# Esquematico_V2.net
KiCad netlist of a schematic drawn in Altium Designer
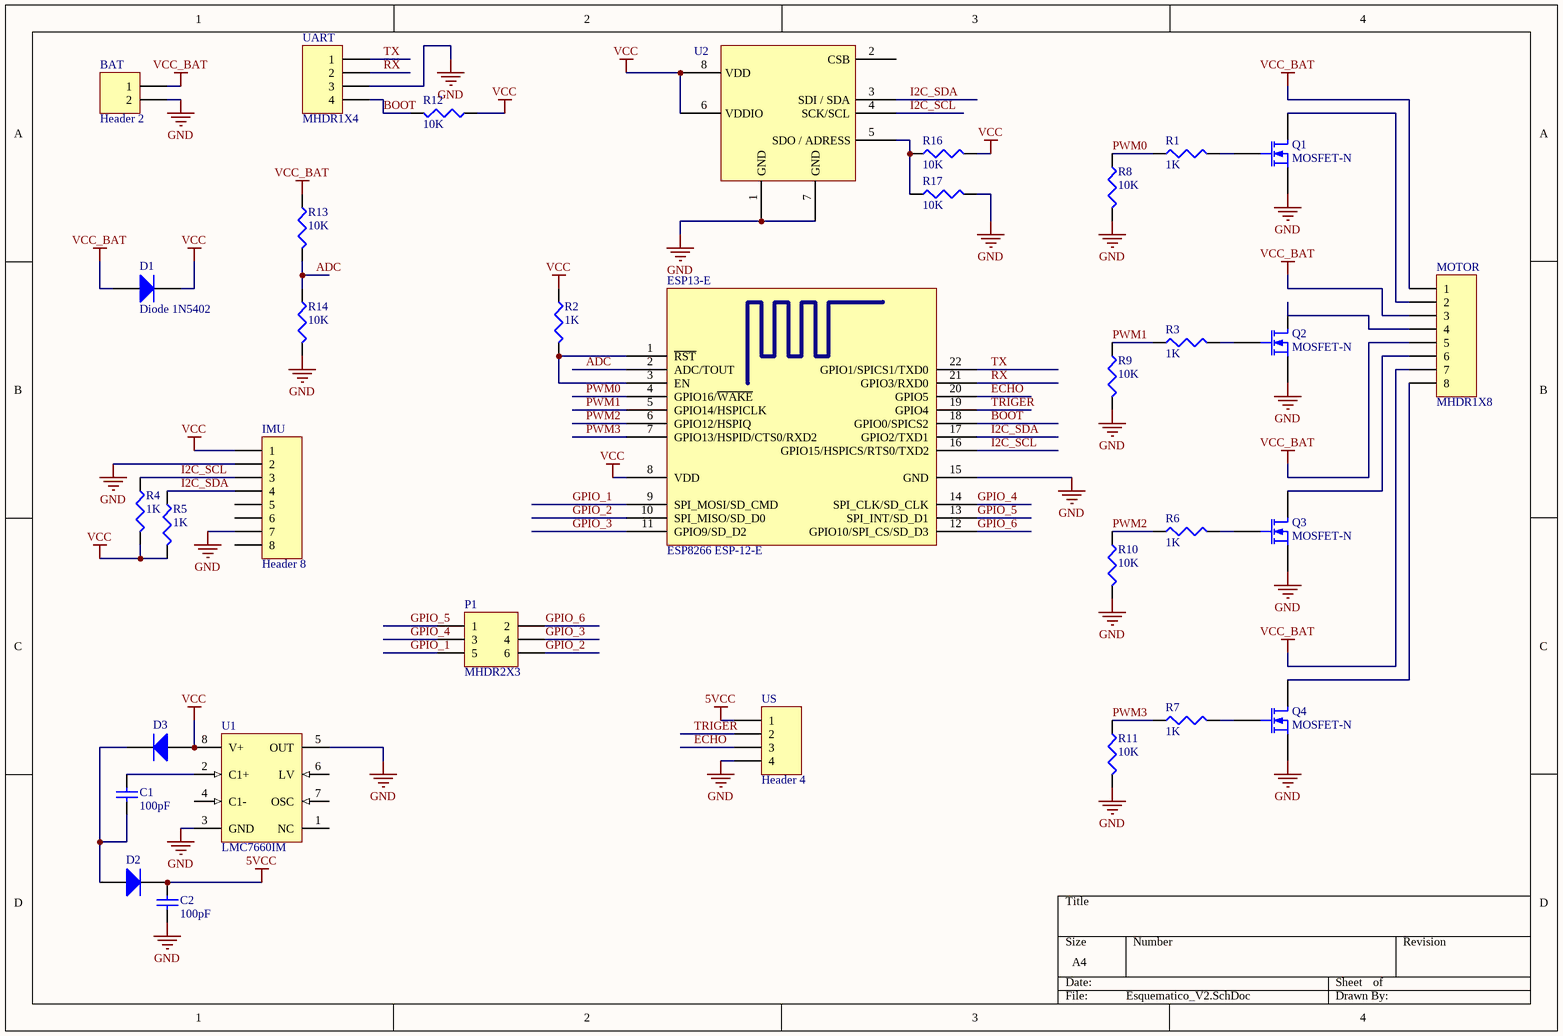
[diagram p0: Esquematico_V2.SchDoc]

(export (version "E")
  (design (tool "Eeschema 10.0.6"))
  (components
    (comp (ref "BAT")
      (value "Header 2")
      (footprint "Miscellaneous Connectors:MHDR1X2")
      (description "Header, 2-Pin")
      (fields (field (name "PUBLISHER") "Altium Limited"))
      (libsource (lib "Miscellaneous Connectors") (part "Header 2"))
    )
    (comp (ref "C1")
      (value "100pF")
      (footprint "Miscellaneous Devices:C0805")
      (description "Capacitor")
      (fields (field (name "Comment") "Cap") (field (name "PUBLISHER") "Altium Limited"))
      (libsource (lib "Miscellaneous Devices") (part "Cap"))
    )
    (comp (ref "C2")
      (value "100pF")
      (footprint "Miscellaneous Devices:C0805")
      (description "Capacitor")
      (fields (field (name "Comment") "Cap") (field (name "PUBLISHER") "Altium Limited"))
      (libsource (lib "Miscellaneous Devices") (part "Cap"))
    )
    (comp (ref "D1")
      (value "Diode 1N5402")
      (footprint "DSO-C2/X2.3")
      (description "3 Amp General Purpose Rectifier")
      (fields (field (name "PUBLISHER") "Altium Limited"))
      (libsource (lib "Miscellaneous Devices") (part "Diode 1N5402"))
    )
    (comp (ref "D2")
      (value "Diode 1N5402")
      (footprint "DSO-C2/Z6.7")
      (description "3 Amp General Purpose Rectifier")
      (fields (field (name "PUBLISHER") "Altium Limited"))
      (libsource (lib "Miscellaneous Devices") (part "Diode 1N5402"))
    )
    (comp (ref "D3")
      (value "Diode 1N5402")
      (footprint "DSO-C2/Z6.7")
      (description "3 Amp General Purpose Rectifier")
      (fields (field (name "PUBLISHER") "Altium Limited"))
      (libsource (lib "Miscellaneous Devices") (part "Diode 1N5402"))
    )
    (comp (ref "ESP13-E")
      (value "ESP8266 ESP-12-E")
      (footprint "ESP8266:ESP8266 ESP-12-E B")
      (libsource (lib "ESP8266") (part "ESP8266 ESP-12-E"))
    )
    (comp (ref "IMU")
      (value "Header 8")
      (footprint "HDR1X8")
      (description "Header, 8-Pin")
      (fields (field (name "PUBLISHER") "Altium Limited"))
      (libsource (lib "Miscellaneous Connectors") (part "Header 8"))
    )
    (comp (ref "MOTOR")
      (value "MHDR1X8")
      (footprint "MHDR1X8")
      (description "Header, 8-Pin")
      (fields (field (name "PUBLISHER") "Altium Limited"))
      (libsource (lib "Miscellaneous Connectors") (part "MHDR1X8"))
    )
    (comp (ref "P1")
      (value "MHDR2X3")
      (footprint "MHDR2X3")
      (description "Header, 3-Pin, Dual row")
      (fields (field (name "PUBLISHER") "Altium Limited"))
      (libsource (lib "Miscellaneous Connectors") (part "MHDR2X3"))
    )
    (comp (ref "Q1")
      (value "MOSFET-N")
      (footprint "PBL - SMD Packages:SOT23-3")
      (description "N-Channel MOSFET")
      (fields (field (name "PUBLISHER") "Altium Limited"))
      (libsource (lib "Miscellaneous Devices") (part "MOSFET-N"))
    )
    (comp (ref "Q2")
      (value "MOSFET-N")
      (footprint "PBL - SMD Packages:SOT23-3")
      (description "N-Channel MOSFET")
      (fields (field (name "PUBLISHER") "Altium Limited"))
      (libsource (lib "Miscellaneous Devices") (part "MOSFET-N"))
    )
    (comp (ref "Q3")
      (value "MOSFET-N")
      (footprint "PBL - SMD Packages:SOT23-3")
      (description "N-Channel MOSFET")
      (fields (field (name "PUBLISHER") "Altium Limited"))
      (libsource (lib "Miscellaneous Devices") (part "MOSFET-N"))
    )
    (comp (ref "Q4")
      (value "MOSFET-N")
      (footprint "PBL - SMD Packages:SOT23-3")
      (description "N-Channel MOSFET")
      (fields (field (name "PUBLISHER") "Altium Limited"))
      (libsource (lib "Miscellaneous Devices") (part "MOSFET-N"))
    )
    (comp (ref "R1")
      (value "1K")
      (footprint "C0805")
      (description "Resistor")
      (fields (field (name "Comment") "Res3") (field (name "PUBLISHER") "Altium Limited"))
      (libsource (lib "Miscellaneous Devices") (part "Res3"))
    )
    (comp (ref "R2")
      (value "1K")
      (footprint "C0805")
      (description "Resistor")
      (fields (field (name "Comment") "Res3") (field (name "PUBLISHER") "Altium Limited"))
      (libsource (lib "Miscellaneous Devices") (part "Res3"))
    )
    (comp (ref "R3")
      (value "1K")
      (footprint "C0805")
      (description "Resistor")
      (fields (field (name "Comment") "Res3") (field (name "PUBLISHER") "Altium Limited"))
      (libsource (lib "Miscellaneous Devices") (part "Res3"))
    )
    (comp (ref "R4")
      (value "1K")
      (footprint "Miscellaneous Devices:C0805")
      (description "Resistor")
      (fields (field (name "Comment") "Res3") (field (name "PUBLISHER") "Altium Limited"))
      (libsource (lib "Miscellaneous Devices") (part "Res3"))
    )
    (comp (ref "R5")
      (value "1K")
      (footprint "Miscellaneous Devices:C0805")
      (description "Resistor")
      (fields (field (name "Comment") "Res3") (field (name "PUBLISHER") "Altium Limited"))
      (libsource (lib "Miscellaneous Devices") (part "Res3"))
    )
    (comp (ref "R6")
      (value "1K")
      (footprint "C0805")
      (description "Resistor")
      (fields (field (name "Comment") "Res3") (field (name "PUBLISHER") "Altium Limited"))
      (libsource (lib "Miscellaneous Devices") (part "Res3"))
    )
    (comp (ref "R7")
      (value "1K")
      (footprint "C0805")
      (description "Resistor")
      (fields (field (name "Comment") "Res3") (field (name "PUBLISHER") "Altium Limited"))
      (libsource (lib "Miscellaneous Devices") (part "Res3"))
    )
    (comp (ref "R8")
      (value "10K")
      (footprint "C0805")
      (description "Resistor")
      (fields (field (name "Comment") "Res3") (field (name "PUBLISHER") "Altium Limited"))
      (libsource (lib "Miscellaneous Devices") (part "Res3"))
    )
    (comp (ref "R9")
      (value "10K")
      (footprint "C0805")
      (description "Resistor")
      (fields (field (name "Comment") "Res3") (field (name "PUBLISHER") "Altium Limited"))
      (libsource (lib "Miscellaneous Devices") (part "Res3"))
    )
    (comp (ref "R10")
      (value "10K")
      (footprint "C0805")
      (description "Resistor")
      (fields (field (name "Comment") "Res3") (field (name "PUBLISHER") "Altium Limited"))
      (libsource (lib "Miscellaneous Devices") (part "Res3"))
    )
    (comp (ref "R11")
      (value "10K")
      (footprint "C0805")
      (description "Resistor")
      (fields (field (name "Comment") "Res3") (field (name "PUBLISHER") "Altium Limited"))
      (libsource (lib "Miscellaneous Devices") (part "Res3"))
    )
    (comp (ref "R12")
      (value "10K")
      (footprint "C0805")
      (description "Resistor")
      (fields (field (name "Comment") "Res3") (field (name "PUBLISHER") "Altium Limited"))
      (libsource (lib "Miscellaneous Devices") (part "Res3"))
    )
    (comp (ref "R13")
      (value "10K")
      (footprint "C0805")
      (description "Resistor")
      (fields (field (name "Comment") "Res3") (field (name "PUBLISHER") "Altium Limited"))
      (libsource (lib "Miscellaneous Devices") (part "Res3"))
    )
    (comp (ref "R14")
      (value "10K")
      (footprint "C0805")
      (description "Resistor")
      (fields (field (name "Comment") "Res3") (field (name "PUBLISHER") "Altium Limited"))
      (libsource (lib "Miscellaneous Devices") (part "Res3"))
    )
    (comp (ref "R16")
      (value "10K")
      (footprint "C0805")
      (description "Resistor")
      (fields (field (name "Comment") "Res3") (field (name "PUBLISHER") "Altium Limited"))
      (libsource (lib "Miscellaneous Devices") (part "Res3"))
    )
    (comp (ref "R17")
      (value "10K")
      (footprint "C0805")
      (description "Resistor")
      (fields (field (name "Comment") "Res3") (field (name "PUBLISHER") "Altium Limited"))
      (libsource (lib "Miscellaneous Devices") (part "Res3"))
    )
    (comp (ref "U1")
      (value "LMC7660IM")
      (footprint "M08A_N")
      (description "Switched Capacitor Voltage Converter, 8-pin Narrow SOIC")
      (fields
        (field (name "MANUFACTURER") "National Semiconductor")
        (field (name "PUBLISHER") "Altium Limited")
      )
      (libsource (lib "NSC Switch Caps") (part "LMC7660IM"))
    )
    (comp (ref "U2")
      (value "BMP280")
      (footprint "LGA-8_BMP280(Primary)")
      (description "Barometro")
      (libsource (lib "BMP280") (part "BMP280"))
    )
    (comp (ref "UART")
      (value "MHDR1X4")
      (footprint "MHDR1X4")
      (description "Header, 4-Pin")
      (fields (field (name "PUBLISHER") "Altium Limited"))
      (libsource (lib "Miscellaneous Connectors") (part "MHDR1X4"))
    )
    (comp (ref "US")
      (value "Header 4")
      (footprint "HDR1X4")
      (description "Header, 4-Pin")
      (fields (field (name "PUBLISHER") "Altium Limited"))
      (libsource (lib "Miscellaneous Connectors") (part "Header 4"))
    )
  )
  (nets
    (net (code "1") (name "/ADC") (class "Default")
      (node (ref "ESP13-E") (pin "2") (pinfunction "ADC/TOUT_2") (pintype "passive"))
      (node (ref "R13") (pin "2") (pinfunction "2_2") (pintype "passive"))
      (node (ref "R14") (pin "1") (pinfunction "1_1") (pintype "passive"))
    )
    (net (code "2") (name "/BOOT") (class "Default")
      (node (ref "ESP13-E") (pin "18") (pinfunction "GPIO0/SPICS2_18") (pintype "passive"))
      (node (ref "R12") (pin "2") (pinfunction "2_2") (pintype "passive"))
      (node (ref "UART") (pin "4") (pinfunction "4_4") (pintype "passive"))
    )
    (net (code "3") (name "/ECHO") (class "Default")
      (node (ref "ESP13-E") (pin "20") (pinfunction "GPIO5_20") (pintype "passive"))
      (node (ref "US") (pin "3") (pinfunction "3_3") (pintype "passive"))
    )
    (net (code "4") (name "/GPIO_1") (class "Default")
      (node (ref "ESP13-E") (pin "9") (pinfunction "SPI_MOSI/SD_CMD_9") (pintype "passive"))
      (node (ref "P1") (pin "5") (pinfunction "5_5") (pintype "passive"))
    )
    (net (code "5") (name "/GPIO_2") (class "Default")
      (node (ref "ESP13-E") (pin "10") (pinfunction "SPI_MISO/SD_D0_10") (pintype "passive"))
      (node (ref "P1") (pin "6") (pinfunction "6_6") (pintype "passive"))
    )
    (net (code "6") (name "/GPIO_3") (class "Default")
      (node (ref "ESP13-E") (pin "11") (pinfunction "GPIO9/SD_D2_11") (pintype "passive"))
      (node (ref "P1") (pin "4") (pinfunction "4_4") (pintype "passive"))
    )
    (net (code "7") (name "/GPIO_4") (class "Default")
      (node (ref "ESP13-E") (pin "14") (pinfunction "SPI_CLK/SD_CLK_14") (pintype "passive"))
      (node (ref "P1") (pin "3") (pinfunction "3_3") (pintype "passive"))
    )
    (net (code "8") (name "/GPIO_5") (class "Default")
      (node (ref "ESP13-E") (pin "13") (pinfunction "SPI_INT/SD_D1_13") (pintype "passive"))
      (node (ref "P1") (pin "1") (pinfunction "1_1") (pintype "passive"))
    )
    (net (code "9") (name "/GPIO_6") (class "Default")
      (node (ref "ESP13-E") (pin "12") (pinfunction "GPIO10/SPI_CS/SD_D3_12") (pintype "passive"))
      (node (ref "P1") (pin "2") (pinfunction "2_2") (pintype "passive"))
    )
    (net (code "10") (name "/I2C_SCL") (class "Default")
      (node (ref "ESP13-E") (pin "16") (pinfunction "GPIO15/HSPICS/RTS0/TXD2_16") (pintype "passive"))
      (node (ref "IMU") (pin "3") (pinfunction "3_3") (pintype "passive"))
      (node (ref "R4") (pin "1") (pinfunction "1_1") (pintype "passive"))
      (node (ref "U2") (pin "4") (pinfunction "SCK/SCL_4") (pintype "passive"))
    )
    (net (code "11") (name "/I2C_SDA") (class "Default")
      (node (ref "ESP13-E") (pin "17") (pinfunction "GPIO2/TXD1_17") (pintype "passive"))
      (node (ref "IMU") (pin "4") (pinfunction "4_4") (pintype "passive"))
      (node (ref "R5") (pin "1") (pinfunction "1_1") (pintype "passive"))
      (node (ref "U2") (pin "3") (pinfunction "SDI_/_SDA_3") (pintype "passive"))
    )
    (net (code "12") (name "/PWM0") (class "Default")
      (node (ref "ESP13-E") (pin "4") (pinfunction "GPIO16/~{WAKE}_4") (pintype "passive"))
      (node (ref "R1") (pin "1") (pinfunction "1_1") (pintype "passive"))
      (node (ref "R8") (pin "1") (pinfunction "1_1") (pintype "passive"))
    )
    (net (code "13") (name "/PWM1") (class "Default")
      (node (ref "ESP13-E") (pin "5") (pinfunction "GPIO14/HSPICLK_5") (pintype "passive"))
      (node (ref "R3") (pin "1") (pinfunction "1_1") (pintype "passive"))
      (node (ref "R9") (pin "1") (pinfunction "1_1") (pintype "passive"))
    )
    (net (code "14") (name "/PWM2") (class "Default")
      (node (ref "ESP13-E") (pin "6") (pinfunction "GPIO12/HSPIQ_6") (pintype "passive"))
      (node (ref "R10") (pin "1") (pinfunction "1_1") (pintype "passive"))
      (node (ref "R6") (pin "1") (pinfunction "1_1") (pintype "passive"))
    )
    (net (code "15") (name "/PWM3") (class "Default")
      (node (ref "ESP13-E") (pin "7") (pinfunction "GPIO13/HSPID/CTS0/RXD2_7") (pintype "passive"))
      (node (ref "R11") (pin "1") (pinfunction "1_1") (pintype "passive"))
      (node (ref "R7") (pin "1") (pinfunction "1_1") (pintype "passive"))
    )
    (net (code "16") (name "/RX") (class "Default")
      (node (ref "ESP13-E") (pin "21") (pinfunction "GPIO3/RXD0_21") (pintype "passive"))
      (node (ref "UART") (pin "2") (pinfunction "2_2") (pintype "passive"))
    )
    (net (code "17") (name "/TRIGER") (class "Default")
      (node (ref "ESP13-E") (pin "19") (pinfunction "GPIO4_19") (pintype "passive"))
      (node (ref "US") (pin "2") (pinfunction "2_2") (pintype "passive"))
    )
    (net (code "18") (name "/TX") (class "Default")
      (node (ref "ESP13-E") (pin "22") (pinfunction "GPIO1/SPICS1/TXD0_22") (pintype "passive"))
      (node (ref "UART") (pin "1") (pinfunction "1_1") (pintype "passive"))
    )
    (net (code "19") (name "5VCC") (class "Default")
      (node (ref "C2") (pin "2") (pinfunction "2_2") (pintype "passive"))
      (node (ref "D2") (pin "2") (pinfunction "K_2") (pintype "passive"))
      (node (ref "US") (pin "1") (pinfunction "1_1") (pintype "passive"))
    )
    (net (code "20") (name "GND") (class "Default")
      (node (ref "BAT") (pin "2") (pinfunction "2_2") (pintype "passive"))
      (node (ref "C2") (pin "1") (pinfunction "1_1") (pintype "passive"))
      (node (ref "ESP13-E") (pin "15") (pinfunction "GND_15") (pintype "passive"))
      (node (ref "IMU") (pin "2") (pinfunction "2_2") (pintype "passive"))
      (node (ref "IMU") (pin "7") (pinfunction "7_7") (pintype "passive"))
      (node (ref "Q1") (pin "3") (pinfunction "S_3") (pintype "passive"))
      (node (ref "Q2") (pin "3") (pinfunction "S_3") (pintype "passive"))
      (node (ref "Q3") (pin "3") (pinfunction "S_3") (pintype "passive"))
      (node (ref "Q4") (pin "3") (pinfunction "S_3") (pintype "passive"))
      (node (ref "R10") (pin "2") (pinfunction "2_2") (pintype "passive"))
      (node (ref "R11") (pin "2") (pinfunction "2_2") (pintype "passive"))
      (node (ref "R14") (pin "2") (pinfunction "2_2") (pintype "passive"))
      (node (ref "R17") (pin "2") (pinfunction "2_2") (pintype "passive"))
      (node (ref "R8") (pin "2") (pinfunction "2_2") (pintype "passive"))
      (node (ref "R9") (pin "2") (pinfunction "2_2") (pintype "passive"))
      (node (ref "U1") (pin "3") (pinfunction "GND_3") (pintype "power_in"))
      (node (ref "U1") (pin "5") (pinfunction "OUT_5") (pintype "power_in"))
      (node (ref "U2") (pin "1") (pinfunction "GND_1") (pintype "passive"))
      (node (ref "U2") (pin "7") (pinfunction "GND_7") (pintype "passive"))
      (node (ref "UART") (pin "3") (pinfunction "3_3") (pintype "passive"))
      (node (ref "US") (pin "4") (pinfunction "4_4") (pintype "passive"))
    )
    (net (code "21") (name "Net-(D2-A)") (class "Default")
      (node (ref "C1") (pin "2") (pinfunction "2_2") (pintype "passive"))
      (node (ref "D2") (pin "1") (pinfunction "A_1") (pintype "passive"))
      (node (ref "D3") (pin "2") (pinfunction "K_2") (pintype "passive"))
    )
    (net (code "22") (name "Net-(ESP13-E-EN)") (class "Default")
      (node (ref "ESP13-E") (pin "1") (pinfunction "~{RST}_1") (pintype "passive"))
      (node (ref "ESP13-E") (pin "3") (pinfunction "EN_3") (pintype "passive"))
      (node (ref "R2") (pin "2") (pinfunction "2_2") (pintype "passive"))
    )
    (net (code "23") (name "Net-(Q1-D)") (class "Default")
      (node (ref "MOTOR") (pin "2") (pinfunction "2_2") (pintype "passive"))
      (node (ref "Q1") (pin "1") (pinfunction "D_1") (pintype "passive"))
    )
    (net (code "24") (name "Net-(Q1-G)") (class "Default")
      (node (ref "Q1") (pin "2") (pinfunction "G_2") (pintype "passive"))
      (node (ref "R1") (pin "2") (pinfunction "2_2") (pintype "passive"))
    )
    (net (code "25") (name "Net-(Q2-D)") (class "Default")
      (node (ref "MOTOR") (pin "4") (pinfunction "4_4") (pintype "passive"))
      (node (ref "Q2") (pin "1") (pinfunction "D_1") (pintype "passive"))
    )
    (net (code "26") (name "Net-(Q2-G)") (class "Default")
      (node (ref "Q2") (pin "2") (pinfunction "G_2") (pintype "passive"))
      (node (ref "R3") (pin "2") (pinfunction "2_2") (pintype "passive"))
    )
    (net (code "27") (name "Net-(Q3-D)") (class "Default")
      (node (ref "MOTOR") (pin "6") (pinfunction "6_6") (pintype "passive"))
      (node (ref "Q3") (pin "1") (pinfunction "D_1") (pintype "passive"))
    )
    (net (code "28") (name "Net-(Q3-G)") (class "Default")
      (node (ref "Q3") (pin "2") (pinfunction "G_2") (pintype "passive"))
      (node (ref "R6") (pin "2") (pinfunction "2_2") (pintype "passive"))
    )
    (net (code "29") (name "Net-(Q4-D)") (class "Default")
      (node (ref "MOTOR") (pin "8") (pinfunction "8_8") (pintype "passive"))
      (node (ref "Q4") (pin "1") (pinfunction "D_1") (pintype "passive"))
    )
    (net (code "30") (name "Net-(Q4-G)") (class "Default")
      (node (ref "Q4") (pin "2") (pinfunction "G_2") (pintype "passive"))
      (node (ref "R7") (pin "2") (pinfunction "2_2") (pintype "passive"))
    )
    (net (code "31") (name "Net-(U1-C1+)") (class "Default")
      (node (ref "C1") (pin "1") (pinfunction "1_1") (pintype "passive"))
      (node (ref "U1") (pin "2") (pinfunction "C1+_2") (pintype "input"))
    )
    (net (code "32") (name "Net-(U2-SDO_{slash}_ADRESS)") (class "Default")
      (node (ref "R16") (pin "1") (pinfunction "1_1") (pintype "passive"))
      (node (ref "R17") (pin "1") (pinfunction "1_1") (pintype "passive"))
      (node (ref "U2") (pin "5") (pinfunction "SDO_/_ADRESS_5") (pintype "passive"))
    )
    (net (code "33") (name "VCC") (class "Default")
      (node (ref "D1") (pin "2") (pinfunction "K_2") (pintype "passive"))
      (node (ref "D3") (pin "1") (pinfunction "A_1") (pintype "passive"))
      (node (ref "ESP13-E") (pin "8") (pinfunction "VDD_8") (pintype "passive"))
      (node (ref "IMU") (pin "1") (pinfunction "1_1") (pintype "passive"))
      (node (ref "R12") (pin "1") (pinfunction "1_1") (pintype "passive"))
      (node (ref "R16") (pin "2") (pinfunction "2_2") (pintype "passive"))
      (node (ref "R2") (pin "1") (pinfunction "1_1") (pintype "passive"))
      (node (ref "R4") (pin "2") (pinfunction "2_2") (pintype "passive"))
      (node (ref "R5") (pin "2") (pinfunction "2_2") (pintype "passive"))
      (node (ref "U1") (pin "8") (pinfunction "V+_8") (pintype "power_in"))
      (node (ref "U2") (pin "6") (pinfunction "VDDIO_6") (pintype "passive"))
      (node (ref "U2") (pin "8") (pinfunction "VDD_8") (pintype "passive"))
    )
    (net (code "34") (name "VCC_BAT") (class "Default")
      (node (ref "BAT") (pin "1") (pinfunction "1_1") (pintype "passive"))
      (node (ref "D1") (pin "1") (pinfunction "A_1") (pintype "passive"))
      (node (ref "MOTOR") (pin "1") (pinfunction "1_1") (pintype "passive"))
      (node (ref "MOTOR") (pin "3") (pinfunction "3_3") (pintype "passive"))
      (node (ref "MOTOR") (pin "5") (pinfunction "5_5") (pintype "passive"))
      (node (ref "MOTOR") (pin "7") (pinfunction "7_7") (pintype "passive"))
      (node (ref "R13") (pin "1") (pinfunction "1_1") (pintype "passive"))
    )
    (net (code "35") (name "unconnected-(IMU-Pad5)") (class "Default")
      (node (ref "IMU") (pin "5") (pinfunction "5_5") (pintype "passive"))
    )
    (net (code "36") (name "unconnected-(IMU-Pad6)") (class "Default")
      (node (ref "IMU") (pin "6") (pinfunction "6_6") (pintype "passive"))
    )
    (net (code "37") (name "unconnected-(IMU-Pad8)") (class "Default")
      (node (ref "IMU") (pin "8") (pinfunction "8_8") (pintype "passive"))
    )
    (net (code "38") (name "unconnected-(U1-C1--Pad4)") (class "Default")
      (node (ref "U1") (pin "4") (pinfunction "C1-_4") (pintype "input"))
    )
    (net (code "39") (name "unconnected-(U1-LV-Pad6)") (class "Default")
      (node (ref "U1") (pin "6") (pinfunction "LV_6") (pintype "input"))
    )
    (net (code "40") (name "unconnected-(U1-NC-Pad1)") (class "Default")
      (node (ref "U1") (pin "1") (pinfunction "NC_1") (pintype "passive"))
    )
    (net (code "41") (name "unconnected-(U1-OSC-Pad7)") (class "Default")
      (node (ref "U1") (pin "7") (pinfunction "OSC_7") (pintype "input"))
    )
    (net (code "42") (name "unconnected-(U2-CSB-Pad2)") (class "Default")
      (node (ref "U2") (pin "2") (pinfunction "CSB_2") (pintype "passive"))
    )
  )
)
